# MCU_main-Sheet_1.net
KiCad netlist of a schematic drawn in Altium Designer
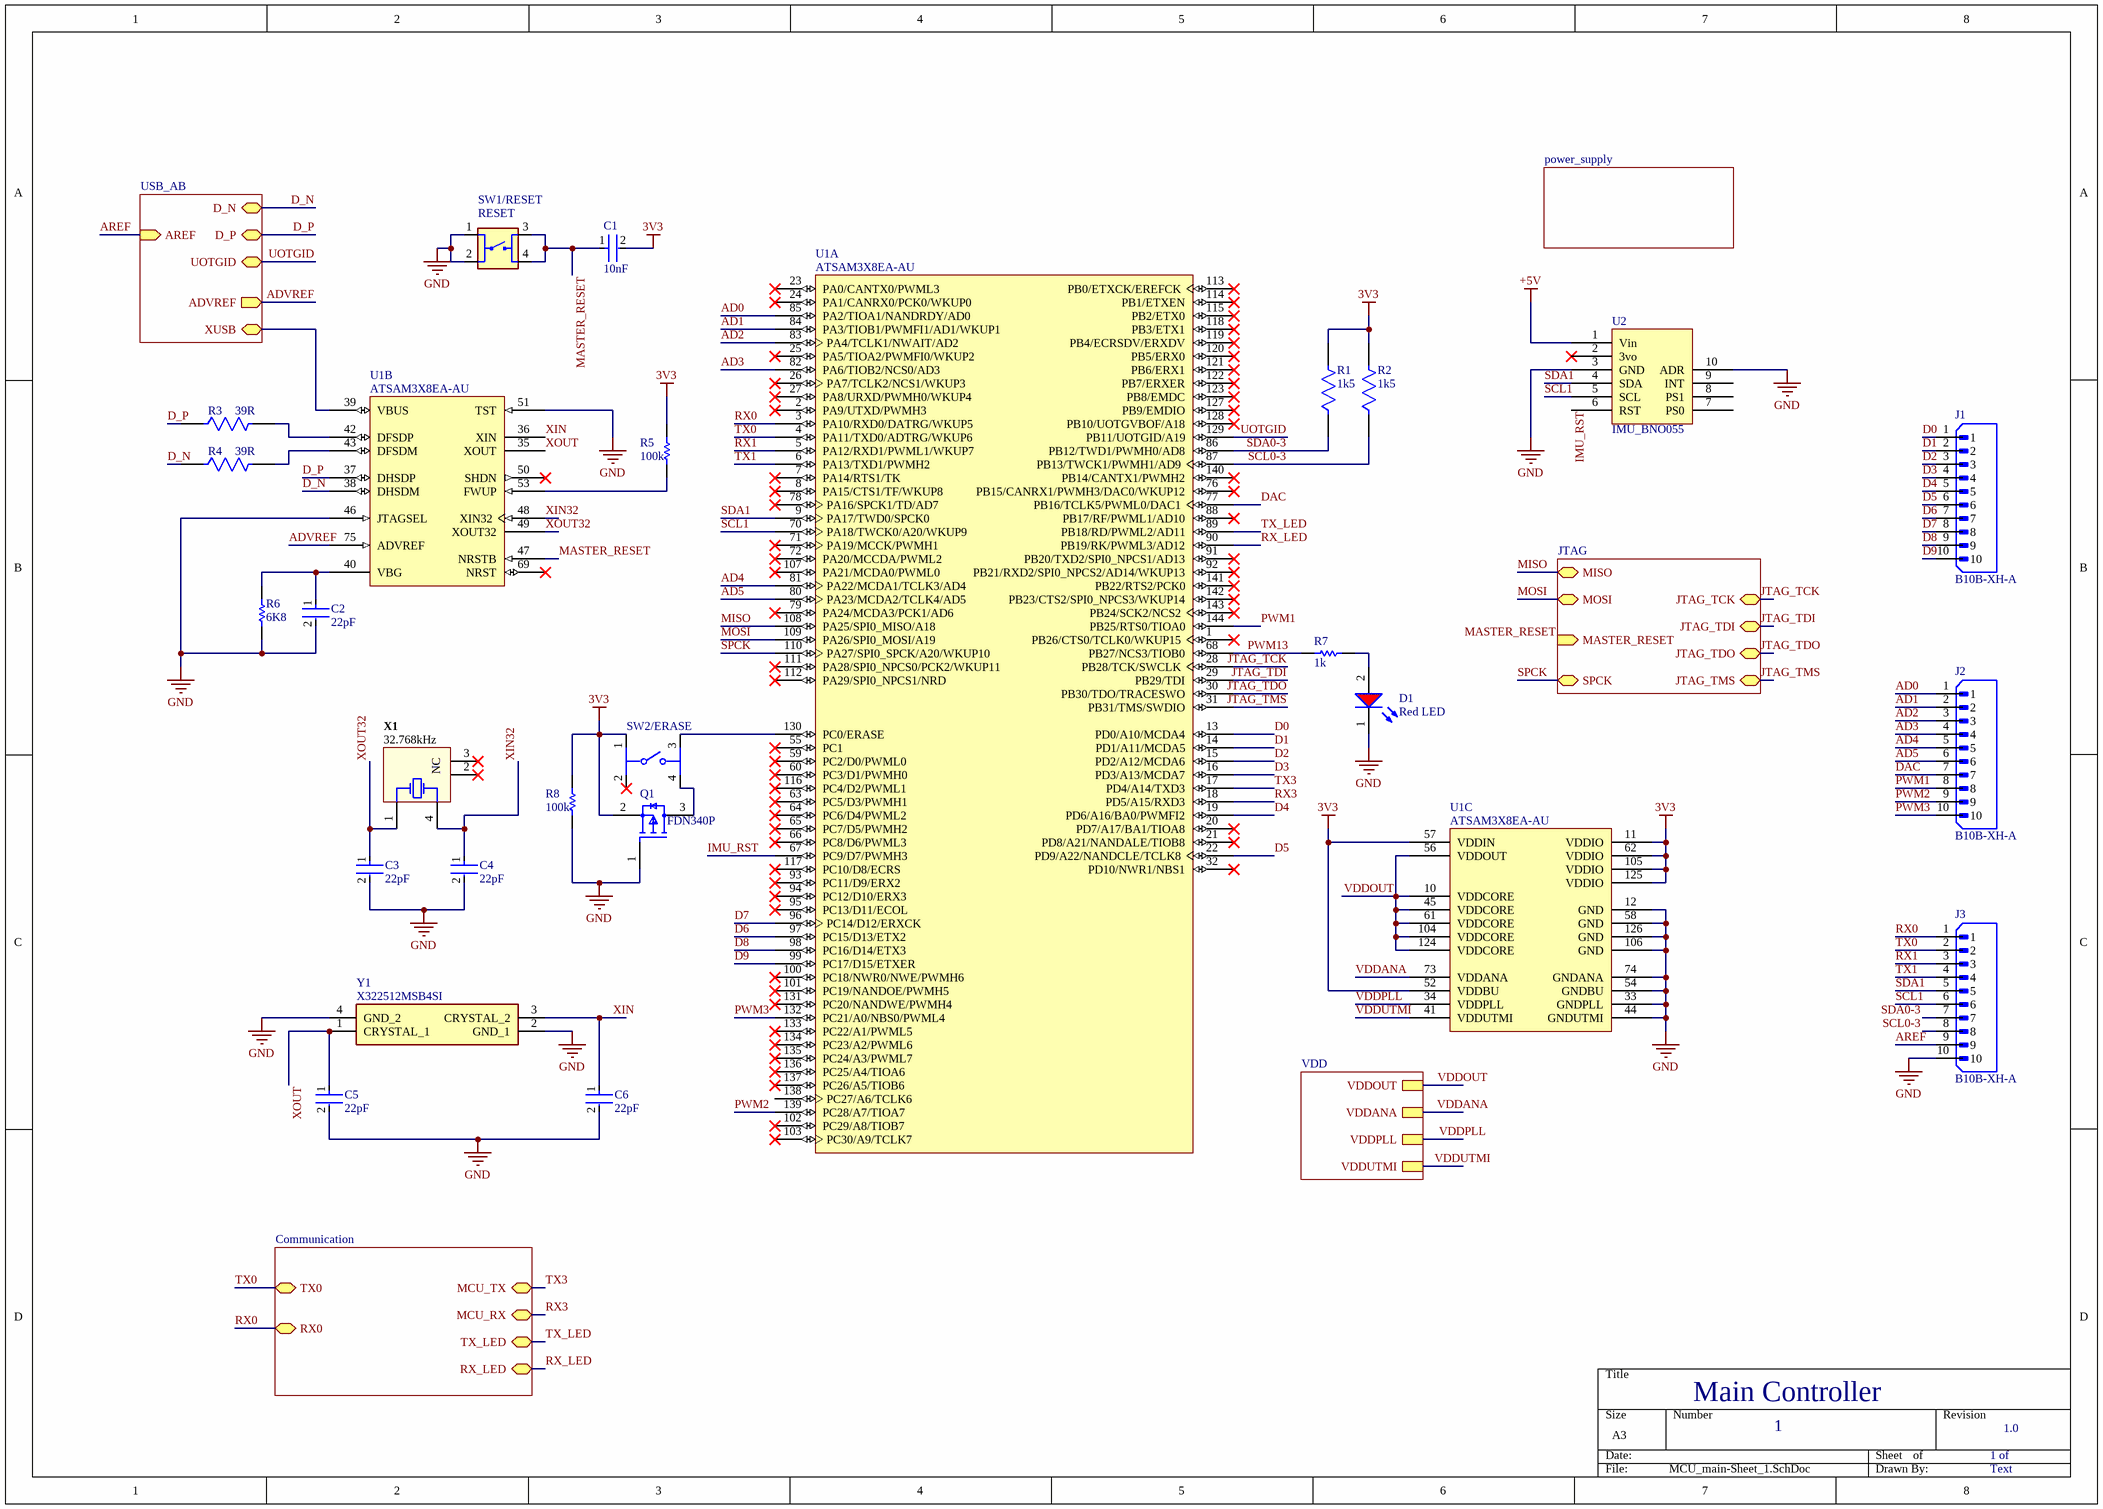
[diagram p0:  MCU_main-Sheet_1.SchDoc]

(export (version "E")
  (design (tool "Eeschema 10.0.6"))
  (components
    (comp (ref "C1")
      (value "10nF")
      (footprint "FP-C0805C-DN-MFG")
      (description "CAP CER 10000PF 200V X7R 0805")
      (fields
        (field (name "OCTOPART") "https://octopart.com/c0805c103k2ractu-kemet-9138347")
        (field (name "MANUFACTURER PART NUMBER") "C0805C103K2RACTU")
      )
      (libsource (lib "Altium Content Vault") (part "b4654b650e69147ec39a6b967a45e02"))
    )
    (comp (ref "C2")
      (value "22pF")
      (footprint "FP-C0805C-DN-MFG")
      (description "Capacitor; Ceramic; Cap; 22.0pF; Tol 5%; SMT; Vol-Rtg 50V; C0G; Tape and Reel")
      (fields
        (field (name "OCTOPART") "https://octopart.com/c0805c220j5gactu-kemet-145470")
        (field (name "MANUFACTURER") "KEMET")
      )
      (libsource (lib "Altium Content Vault") (part "b4654b650e69147ec39a6b967a45e02"))
    )
    (comp (ref "C3")
      (value "22pF")
      (footprint "FP-C0805C-DN-MFG")
      (description "Capacitor; Ceramic; Cap; 22.0pF; Tol 5%; SMT; Vol-Rtg 50V; C0G; Tape and Reel")
      (fields
        (field (name "OCTOPART") "https://octopart.com/c0805c220j5gactu-kemet-145470")
        (field (name "MANUFACTURER") "KEMET")
      )
      (libsource (lib "Altium Content Vault") (part "b4654b650e69147ec39a6b967a45e02"))
    )
    (comp (ref "C4")
      (value "22pF")
      (footprint "FP-C0805C-DN-MFG")
      (description "Capacitor; Ceramic; Cap; 22.0pF; Tol 5%; SMT; Vol-Rtg 50V; C0G; Tape and Reel")
      (fields
        (field (name "OCTOPART") "https://octopart.com/c0805c220j5gactu-kemet-145470")
        (field (name "MANUFACTURER") "KEMET")
      )
      (libsource (lib "Altium Content Vault") (part "b4654b650e69147ec39a6b967a45e02"))
    )
    (comp (ref "C5")
      (value "22pF")
      (footprint "FP-C0805C-DN-MFG")
      (description "Capacitor; Ceramic; Cap; 22.0pF; Tol 5%; SMT; Vol-Rtg 50V; C0G; Tape and Reel")
      (fields
        (field (name "OCTOPART") "https://octopart.com/c0805c220j5gactu-kemet-145470")
        (field (name "MANUFACTURER") "KEMET")
      )
      (libsource (lib "Altium Content Vault") (part "b4654b650e69147ec39a6b967a45e02"))
    )
    (comp (ref "C6")
      (value "22pF")
      (footprint "FP-C0805C-DN-MFG")
      (description "Capacitor; Ceramic; Cap; 22.0pF; Tol 5%; SMT; Vol-Rtg 50V; C0G; Tape and Reel")
      (fields
        (field (name "OCTOPART") "https://octopart.com/c0805c220j5gactu-kemet-145470")
        (field (name "MANUFACTURER") "KEMET")
      )
      (libsource (lib "Altium Content Vault") (part "b4654b650e69147ec39a6b967a45e02"))
    )
    (comp (ref "D1")
      (value "Red LED")
      (footprint "WL-SMCW_0603_150060xx75000")
      (description "LED Low-Power Uni-Color Red 630nm 2V 2-Pin Chip 0603(1608Metric) T/R")
      (libsource (lib "Altium Content Vault") (part "LED_Red_2A-1K"))
    )
    (comp (ref "J1")
      (value "B10B-XH-A")
      (footprint "JST_B10B-XH-A")
      (fields (field (name "MF") "{'manufacturer': u'JST Sales America Inc.'}"))
      (libsource (lib "B10B-XH-A") (part "B10B-XH-A"))
    )
    (comp (ref "J2")
      (value "B10B-XH-A")
      (footprint "JST_B10B-XH-A")
      (fields (field (name "MF") "{'manufacturer': u'JST Sales America Inc.'}"))
      (libsource (lib "B10B-XH-A") (part "B10B-XH-A"))
    )
    (comp (ref "J3")
      (value "B10B-XH-A")
      (footprint "JST_B10B-XH-A")
      (fields (field (name "MF") "{'manufacturer': u'JST Sales America Inc.'}"))
      (libsource (lib "B10B-XH-A") (part "B10B-XH-A"))
    )
    (comp (ref "Q1")
      (value "FDN340P")
      (footprint "FP-527AG-MFG")
      (description "MOSFET P-CH 20V 2A SSOT3")
      (libsource (lib "Altium Content Vault") (part "d23f43cc42f60b967b7caccf14518fd"))
    )
    (comp (ref "R1")
      (value "1k5")
      (footprint "FP-RT0805-MFG")
      (description "RES SMD 1.5K OHM 0.25% 1/8W 0805")
      (fields
        (field (name "OCTOPART") "https://octopart.com/rt0805cre071k5l-yageo-1182744")
        (field (name "MANUFACTURER PART NUMBER") "RT0805CRE071K5L")
      )
      (libsource (lib "Altium Content Vault") (part "1029c3af85768c4190bb7ad29bc67b5"))
    )
    (comp (ref "R2")
      (value "1k5")
      (footprint "FP-RT0805-MFG")
      (description "RES SMD 1.5K OHM 0.25% 1/8W 0805")
      (fields
        (field (name "OCTOPART") "https://octopart.com/rt0805cre071k5l-yageo-1182744")
        (field (name "MANUFACTURER PART NUMBER") "RT0805CRE071K5L")
      )
      (libsource (lib "Altium Content Vault") (part "1029c3af85768c4190bb7ad29bc67b5"))
    )
    (comp (ref "R3")
      (value "39R")
      (footprint "FP-RK73H2A-MFG")
      (description "39Ω ±1% 0.25W Chip Resistor 0805 Flat Chip (Anti-Sulfuration) AEC-Q200 Qualified")
      (fields (field (name "TOLERANCE") "1%"))
      (libsource (lib "Altium Content Vault") (part "1029c3af85768c4190bb7ad29bc67b5"))
    )
    (comp (ref "R4")
      (value "39R")
      (footprint "FP-RK73H2A-MFG")
      (description "39Ω ±1% 0.25W Chip Resistor 0805 Flat Chip (Anti-Sulfuration) AEC-Q200 Qualified")
      (fields (field (name "TOLERANCE") "1%"))
      (libsource (lib "Altium Content Vault") (part "1029c3af85768c4190bb7ad29bc67b5"))
    )
    (comp (ref "R5")
      (value "100k")
      (footprint "RESC2013X50X30ML20T20")
      (fields (field (name "MANUFACTURER") "Vishay Dale") (field (name "PART NUMBER") "CRCW0805100KJNEA"))
      (libsource (lib "Altium Content Vault") (part "RES"))
    )
    (comp (ref "R6")
      (value "6K8")
      (footprint "RESC2013X50X30LL20T20")
      (fields (field (name "MANUFACTURER") "Vishay Dale") (field (name "PART NUMBER") "CRCW08056K80JNEA"))
      (libsource (lib "Altium Content Vault") (part "RES"))
    )
    (comp (ref "R7")
      (value "1k")
      (footprint "RESC2013X60X35ML10T20")
      (description "Chip Resistor, 1 KOhm, +/- 1%, 125 mW, -55 to 155 degC, 0805 (2012 Metric), RoHS, Tape and Reel")
      (fields (field (name "TOLERANCE") "1%") (field (name "MANUFACTURER") "Yageo"))
      (libsource (lib "Altium Content Vault") (part "RES-2"))
    )
    (comp (ref "R8")
      (value "100k")
      (footprint "RESC2013X50X30ML20T20")
      (fields (field (name "MANUFACTURER") "Vishay Dale") (field (name "PART NUMBER") "CRCW0805100KJNEA"))
      (libsource (lib "Altium Content Vault") (part "RES"))
    )
    (comp (ref "SW1/RESET")
      (value "RESET")
      (footprint "TE_4-1437565-9")
      (description "Alcoswitch, Switch, Tactile, 50 mA, SPST, Pushbutton, Off[On], FSM6JSMA ¦ TE Connectivity FSM6JSMA")
      (fields (field (name "MF") "TE Connectivity") (field (name "MP") "FSM6JSMA"))
      (libsource (lib "4-1437565-9") (part "4-1437565-9"))
    )
    (comp (ref "SW2/ERASE")
      (value "3-1825910-1")
      (footprint "FP-3-1825910-1-MFG")
      (description "SWITCH TACTILE SPST-NO 0.05A 24V")
      (fields
        (field (name "MANUFACTURER") "TE Connectivity")
        (field (name "OCTOPART") "https://octopart.com/3-1825910-1-te+connectivity-46506874")
      )
      (libsource (lib "Altium Content Vault") (part "b8895f3f4cefb76e1819d2863dba89b"))
    )
    (comp (ref "U1")
      (value "ATSAM3X8EA-AU")
      (footprint "LQFP144_M")
      (fields (field (name "MANUFACTURER") "Atmel"))
      (libsource (lib "Altium Content Vault") (part "ATML-ATSAM3X-LQFP-144"))
    )
    (comp (ref "U2")
      (value "IMU_BNO055")
      (footprint "IMU_BNO055-Footprint-1")
      (description "IMU Sensor")
      (libsource (lib "EDR_Omni_Robot") (part "IMU_BNO055-Symbol-1"))
    )
    (comp (ref "X1")
      (value "32.768kHz")
      (footprint "ABRA-ABS25-4_V")
      (fields (field (name "TOLERANCE") "20PPM") (field (name "MANUFACTURER") "Abracon"))
      (libsource (lib "Altium Content Vault") (part "ABRA-XTAL_1-4-4"))
    )
    (comp (ref "Y1")
      (value "X322512MSB4SI")
      (footprint "SamacSys:X322512MSB4SI")
      (description "Crystal or Oscillator")
      (libsource (lib "*") (part "X322512MSB4SI"))
    )
  )
  (nets
    (net (code "1") (name "+5V") (class "Default")
      (node (ref "U2") (pin "1") (pinfunction "Vin_1") (pintype "passive"))
    )
    (net (code "2") (name "/AD0") (class "Default")
      (node (ref "J2") (pin "1") (pinfunction "1_1") (pintype "passive"))
      (node (ref "U1") (pin "85") (pinfunction "PA2/TIOA1/NANDRDY/AD0_85") (pintype "bidirectional"))
    )
    (net (code "3") (name "/AD1") (class "Default")
      (node (ref "J2") (pin "2") (pinfunction "2_2") (pintype "passive"))
      (node (ref "U1") (pin "84") (pinfunction "PA3/TIOB1/PWMFI1/AD1/WKUP1_84") (pintype "bidirectional"))
    )
    (net (code "4") (name "/AD2") (class "Default")
      (node (ref "J2") (pin "3") (pinfunction "3_3") (pintype "passive"))
      (node (ref "U1") (pin "83") (pinfunction "PA4/TCLK1/NWAIT/AD2_83") (pintype "bidirectional"))
    )
    (net (code "5") (name "/AD3") (class "Default")
      (node (ref "J2") (pin "4") (pinfunction "4_4") (pintype "passive"))
      (node (ref "U1") (pin "82") (pinfunction "PA6/TIOB2/NCS0/AD3_82") (pintype "bidirectional"))
    )
    (net (code "6") (name "/AD4") (class "Default")
      (node (ref "J2") (pin "5") (pinfunction "5_5") (pintype "passive"))
      (node (ref "U1") (pin "81") (pinfunction "PA22/MCDA1/TCLK3/AD4_81") (pintype "bidirectional"))
    )
    (net (code "7") (name "/AD5") (class "Default")
      (node (ref "J2") (pin "6") (pinfunction "6_6") (pintype "passive"))
      (node (ref "U1") (pin "80") (pinfunction "PA23/MCDA2/TCLK4/AD5_80") (pintype "bidirectional"))
    )
    (net (code "8") (name "/ADVREF") (class "Default")
      (node (ref "U1") (pin "75") (pinfunction "ADVREF_75") (pintype "input"))
    )
    (net (code "9") (name "/AREF") (class "Default")
      (node (ref "J3") (pin "9") (pinfunction "9_9") (pintype "passive"))
    )
    (net (code "10") (name "/D0") (class "Default")
      (node (ref "J1") (pin "1") (pinfunction "1_1") (pintype "passive"))
      (node (ref "U1") (pin "13") (pinfunction "PD0/A10/MCDA4_13") (pintype "bidirectional"))
    )
    (net (code "11") (name "/D1") (class "Default")
      (node (ref "J1") (pin "2") (pinfunction "2_2") (pintype "passive"))
      (node (ref "U1") (pin "14") (pinfunction "PD1/A11/MCDA5_14") (pintype "bidirectional"))
    )
    (net (code "12") (name "/D2") (class "Default")
      (node (ref "J1") (pin "3") (pinfunction "3_3") (pintype "passive"))
      (node (ref "U1") (pin "15") (pinfunction "PD2/A12/MCDA6_15") (pintype "bidirectional"))
    )
    (net (code "13") (name "/D3") (class "Default")
      (node (ref "J1") (pin "4") (pinfunction "4_4") (pintype "passive"))
      (node (ref "U1") (pin "16") (pinfunction "PD3/A13/MCDA7_16") (pintype "bidirectional"))
    )
    (net (code "14") (name "/D4") (class "Default")
      (node (ref "J1") (pin "5") (pinfunction "5_5") (pintype "passive"))
      (node (ref "U1") (pin "19") (pinfunction "PD6/A16/BA0/PWMFI2_19") (pintype "bidirectional"))
    )
    (net (code "15") (name "/D5") (class "Default")
      (node (ref "J1") (pin "6") (pinfunction "6_6") (pintype "passive"))
      (node (ref "U1") (pin "22") (pinfunction "PD9/A22/NANDCLE/TCLK8_22") (pintype "bidirectional"))
    )
    (net (code "16") (name "/D6") (class "Default")
      (node (ref "J1") (pin "7") (pinfunction "7_7") (pintype "passive"))
      (node (ref "U1") (pin "97") (pinfunction "PC15/D13/ETX2_97") (pintype "bidirectional"))
    )
    (net (code "17") (name "/D7") (class "Default")
      (node (ref "J1") (pin "8") (pinfunction "8_8") (pintype "passive"))
      (node (ref "U1") (pin "96") (pinfunction "PC14/D12/ERXCK_96") (pintype "bidirectional"))
    )
    (net (code "18") (name "/D8") (class "Default")
      (node (ref "J1") (pin "9") (pinfunction "9_9") (pintype "passive"))
      (node (ref "U1") (pin "98") (pinfunction "PC16/D14/ETX3_98") (pintype "bidirectional"))
    )
    (net (code "19") (name "/D9") (class "Default")
      (node (ref "J1") (pin "10") (pinfunction "10_10") (pintype "passive"))
      (node (ref "U1") (pin "99") (pinfunction "PC17/D15/ETXER_99") (pintype "bidirectional"))
    )
    (net (code "20") (name "/DAC") (class "Default")
      (node (ref "J2") (pin "7") (pinfunction "7_7") (pintype "passive"))
      (node (ref "U1") (pin "77") (pinfunction "PB16/TCLK5/PWML0/DAC1_77") (pintype "bidirectional"))
    )
    (net (code "21") (name "/D_N") (class "Default")
      (node (ref "R4") (pin "1") (pinfunction "1_1") (pintype "passive"))
      (node (ref "U1") (pin "38") (pinfunction "DHSDM_38") (pintype "bidirectional"))
    )
    (net (code "22") (name "/D_P") (class "Default")
      (node (ref "R3") (pin "1") (pinfunction "1_1") (pintype "passive"))
      (node (ref "U1") (pin "37") (pinfunction "DHSDP_37") (pintype "bidirectional"))
    )
    (net (code "23") (name "/IMU_RST") (class "Default")
      (node (ref "U1") (pin "67") (pinfunction "PC9/D7/PWMH3_67") (pintype "bidirectional"))
      (node (ref "U2") (pin "6") (pinfunction "RST_6") (pintype "passive"))
    )
    (net (code "24") (name "/JTAG_TCK") (class "Default")
      (node (ref "U1") (pin "28") (pinfunction "PB28/TCK/SWCLK_28") (pintype "bidirectional"))
    )
    (net (code "25") (name "/JTAG_TDI") (class "Default")
      (node (ref "U1") (pin "29") (pinfunction "PB29/TDI_29") (pintype "bidirectional"))
    )
    (net (code "26") (name "/JTAG_TDO") (class "Default")
      (node (ref "U1") (pin "30") (pinfunction "PB30/TDO/TRACESWO_30") (pintype "bidirectional"))
    )
    (net (code "27") (name "/JTAG_TMS") (class "Default")
      (node (ref "U1") (pin "31") (pinfunction "PB31/TMS/SWDIO_31") (pintype "bidirectional"))
    )
    (net (code "28") (name "/MASTER_RESET") (class "Default")
      (node (ref "C1") (pin "1") (pinfunction "1_1") (pintype "passive"))
      (node (ref "SW1/RESET") (pin "3") (pinfunction "3_3") (pintype "passive"))
      (node (ref "SW1/RESET") (pin "4") (pinfunction "4_4") (pintype "passive"))
      (node (ref "U1") (pin "47") (pinfunction "NRSTB_47") (pintype "input"))
    )
    (net (code "29") (name "/MISO") (class "Default")
      (node (ref "U1") (pin "108") (pinfunction "PA25/SPI0_MISO/A18_108") (pintype "bidirectional"))
    )
    (net (code "30") (name "/MOSI") (class "Default")
      (node (ref "U1") (pin "109") (pinfunction "PA26/SPI0_MOSI/A19_109") (pintype "bidirectional"))
    )
    (net (code "31") (name "/PWM1") (class "Default")
      (node (ref "J2") (pin "8") (pinfunction "8_8") (pintype "passive"))
      (node (ref "U1") (pin "144") (pinfunction "PB25/RTS0/TIOA0_144") (pintype "bidirectional"))
    )
    (net (code "32") (name "/PWM2") (class "Default")
      (node (ref "J2") (pin "9") (pinfunction "9_9") (pintype "passive"))
      (node (ref "U1") (pin "139") (pinfunction "PC28/A7/TIOA7_139") (pintype "bidirectional"))
    )
    (net (code "33") (name "/PWM3") (class "Default")
      (node (ref "J2") (pin "10") (pinfunction "10_10") (pintype "passive"))
      (node (ref "U1") (pin "132") (pinfunction "PC21/A0/NBS0/PWML4_132") (pintype "bidirectional"))
    )
    (net (code "34") (name "/PWM13") (class "Default")
      (node (ref "R7") (pin "2") (pinfunction "2_2") (pintype "passive"))
      (node (ref "U1") (pin "68") (pinfunction "PB27/NCS3/TIOB0_68") (pintype "bidirectional"))
    )
    (net (code "35") (name "/RX0") (class "Default")
      (node (ref "J3") (pin "1") (pinfunction "1_1") (pintype "passive"))
      (node (ref "U1") (pin "3") (pinfunction "PA10/RXD0/DATRG/WKUP5_3") (pintype "bidirectional"))
    )
    (net (code "36") (name "/RX1") (class "Default")
      (node (ref "J3") (pin "3") (pinfunction "3_3") (pintype "passive"))
      (node (ref "U1") (pin "5") (pinfunction "PA12/RXD1/PWML1/WKUP7_5") (pintype "bidirectional"))
    )
    (net (code "37") (name "/RX3") (class "Default")
      (node (ref "U1") (pin "18") (pinfunction "PD5/A15/RXD3_18") (pintype "bidirectional"))
    )
    (net (code "38") (name "/RX_LED") (class "Default")
      (node (ref "U1") (pin "90") (pinfunction "PB19/RK/PWML3/AD12_90") (pintype "bidirectional"))
    )
    (net (code "39") (name "/SCL0-3") (class "Default")
      (node (ref "J3") (pin "8") (pinfunction "8_8") (pintype "passive"))
      (node (ref "R2") (pin "1") (pinfunction "1_1") (pintype "passive"))
      (node (ref "U1") (pin "87") (pinfunction "PB13/TWCK1/PWMH1/AD9_87") (pintype "bidirectional"))
    )
    (net (code "40") (name "/SCL1") (class "Default")
      (node (ref "J3") (pin "6") (pinfunction "6_6") (pintype "passive"))
      (node (ref "U1") (pin "70") (pinfunction "PA18/TWCK0/A20/WKUP9_70") (pintype "bidirectional"))
      (node (ref "U2") (pin "5") (pinfunction "SCL_5") (pintype "passive"))
    )
    (net (code "41") (name "/SDA0-3") (class "Default")
      (node (ref "J3") (pin "7") (pinfunction "7_7") (pintype "passive"))
      (node (ref "R1") (pin "1") (pinfunction "1_1") (pintype "passive"))
      (node (ref "U1") (pin "86") (pinfunction "PB12/TWD1/PWMH0/AD8_86") (pintype "bidirectional"))
    )
    (net (code "42") (name "/SDA1") (class "Default")
      (node (ref "J3") (pin "5") (pinfunction "5_5") (pintype "passive"))
      (node (ref "U1") (pin "9") (pinfunction "PA17/TWD0/SPCK0_9") (pintype "bidirectional"))
      (node (ref "U2") (pin "4") (pinfunction "SDA_4") (pintype "passive"))
    )
    (net (code "43") (name "/SPCK") (class "Default")
      (node (ref "U1") (pin "110") (pinfunction "PA27/SPI0_SPCK/A20/WKUP10_110") (pintype "bidirectional"))
    )
    (net (code "44") (name "/TX0") (class "Default")
      (node (ref "J3") (pin "2") (pinfunction "2_2") (pintype "passive"))
      (node (ref "U1") (pin "4") (pinfunction "PA11/TXD0/ADTRG/WKUP6_4") (pintype "bidirectional"))
    )
    (net (code "45") (name "/TX1") (class "Default")
      (node (ref "J3") (pin "4") (pinfunction "4_4") (pintype "passive"))
      (node (ref "U1") (pin "6") (pinfunction "PA13/TXD1/PWMH2_6") (pintype "bidirectional"))
    )
    (net (code "46") (name "/TX3") (class "Default")
      (node (ref "U1") (pin "17") (pinfunction "PD4/A14/TXD3_17") (pintype "bidirectional"))
    )
    (net (code "47") (name "/TX_LED") (class "Default")
      (node (ref "U1") (pin "89") (pinfunction "PB18/RD/PWML2/AD11_89") (pintype "bidirectional"))
    )
    (net (code "48") (name "/UOTGID") (class "Default")
      (node (ref "U1") (pin "129") (pinfunction "PB11/UOTGID/A19_129") (pintype "bidirectional"))
    )
    (net (code "49") (name "/VDDANA") (class "Default")
      (node (ref "U1") (pin "73") (pinfunction "VDDANA_73") (pintype "power_in"))
    )
    (net (code "50") (name "/VDDOUT") (class "Default")
      (node (ref "U1") (pin "10") (pinfunction "VDDCORE_10") (pintype "power_in"))
      (node (ref "U1") (pin "104") (pinfunction "VDDCORE_104") (pintype "power_in"))
      (node (ref "U1") (pin "124") (pinfunction "VDDCORE_124") (pintype "power_in"))
      (node (ref "U1") (pin "45") (pinfunction "VDDCORE_45") (pintype "power_in"))
      (node (ref "U1") (pin "56") (pinfunction "VDDOUT_56") (pintype "power_in"))
      (node (ref "U1") (pin "61") (pinfunction "VDDCORE_61") (pintype "power_in"))
    )
    (net (code "51") (name "/VDDPLL") (class "Default")
      (node (ref "U1") (pin "34") (pinfunction "VDDPLL_34") (pintype "power_in"))
    )
    (net (code "52") (name "/VDDUTMI") (class "Default")
      (node (ref "U1") (pin "41") (pinfunction "VDDUTMI_41") (pintype "power_in"))
    )
    (net (code "53") (name "/XIN") (class "Default")
      (node (ref "C6") (pin "1") (pinfunction "1_1") (pintype "passive"))
      (node (ref "U1") (pin "36") (pinfunction "XIN_36") (pintype "passive"))
      (node (ref "Y1") (pin "3") (pinfunction "CRYSTAL_2_3") (pintype "passive"))
    )
    (net (code "54") (name "/XIN32") (class "Default")
      (node (ref "C4") (pin "1") (pinfunction "1_1") (pintype "passive"))
      (node (ref "U1") (pin "48") (pinfunction "XIN32_48") (pintype "input"))
      (node (ref "X1") (pin "4") (pinfunction "X2_4") (pintype "passive"))
    )
    (net (code "55") (name "/XOUT") (class "Default")
      (node (ref "C5") (pin "1") (pinfunction "1_1") (pintype "passive"))
      (node (ref "U1") (pin "35") (pinfunction "XOUT_35") (pintype "passive"))
      (node (ref "Y1") (pin "1") (pinfunction "CRYSTAL_1_1") (pintype "passive"))
    )
    (net (code "56") (name "/XOUT32") (class "Default")
      (node (ref "C3") (pin "1") (pinfunction "1_1") (pintype "passive"))
      (node (ref "U1") (pin "49") (pinfunction "XOUT32_49") (pintype "passive"))
      (node (ref "X1") (pin "1") (pinfunction "X1_1") (pintype "passive"))
    )
    (net (code "57") (name "/XUSB") (class "Default")
      (node (ref "U1") (pin "39") (pinfunction "VBUS_39") (pintype "bidirectional"))
    )
    (net (code "58") (name "3V3") (class "Default")
      (node (ref "C1") (pin "2") (pinfunction "2_2") (pintype "passive"))
      (node (ref "Q1") (pin "2") (pinfunction "S_2") (pintype "passive"))
      (node (ref "R1") (pin "2") (pinfunction "2_2") (pintype "passive"))
      (node (ref "R2") (pin "2") (pinfunction "2_2") (pintype "passive"))
      (node (ref "R5") (pin "2") (pinfunction "2_2") (pintype "passive"))
      (node (ref "R8") (pin "2") (pinfunction "2_2") (pintype "passive"))
      (node (ref "SW2/ERASE") (pin "1") (pinfunction "1_1") (pintype "passive"))
      (node (ref "U1") (pin "105") (pinfunction "VDDIO_105") (pintype "power_in"))
      (node (ref "U1") (pin "11") (pinfunction "VDDIO_11") (pintype "power_in"))
      (node (ref "U1") (pin "125") (pinfunction "VDDIO_125") (pintype "power_in"))
      (node (ref "U1") (pin "52") (pinfunction "VDDBU_52") (pintype "power_in"))
      (node (ref "U1") (pin "57") (pinfunction "VDDIN_57") (pintype "power_in"))
      (node (ref "U1") (pin "62") (pinfunction "VDDIO_62") (pintype "power_in"))
    )
    (net (code "59") (name "GND") (class "Default")
      (node (ref "C2") (pin "2") (pinfunction "2_2") (pintype "passive"))
      (node (ref "C3") (pin "2") (pinfunction "2_2") (pintype "passive"))
      (node (ref "C4") (pin "2") (pinfunction "2_2") (pintype "passive"))
      (node (ref "C5") (pin "2") (pinfunction "2_2") (pintype "passive"))
      (node (ref "C6") (pin "2") (pinfunction "2_2") (pintype "passive"))
      (node (ref "D1") (pin "1") (pinfunction "K_1") (pintype "passive"))
      (node (ref "J3") (pin "10") (pinfunction "10_10") (pintype "passive"))
      (node (ref "Q1") (pin "1") (pinfunction "G_1") (pintype "passive"))
      (node (ref "R6") (pin "1") (pinfunction "1_1") (pintype "passive"))
      (node (ref "R8") (pin "1") (pinfunction "1_1") (pintype "passive"))
      (node (ref "SW1/RESET") (pin "1") (pinfunction "1_1") (pintype "passive"))
      (node (ref "SW1/RESET") (pin "2") (pinfunction "2_2") (pintype "passive"))
      (node (ref "U1") (pin "106") (pinfunction "GND_106") (pintype "power_in"))
      (node (ref "U1") (pin "12") (pinfunction "GND_12") (pintype "power_in"))
      (node (ref "U1") (pin "126") (pinfunction "GND_126") (pintype "power_in"))
      (node (ref "U1") (pin "33") (pinfunction "GNDPLL_33") (pintype "power_in"))
      (node (ref "U1") (pin "44") (pinfunction "GNDUTMI_44") (pintype "power_in"))
      (node (ref "U1") (pin "46") (pinfunction "JTAGSEL_46") (pintype "input"))
      (node (ref "U1") (pin "51") (pinfunction "TST_51") (pintype "input"))
      (node (ref "U1") (pin "54") (pinfunction "GNDBU_54") (pintype "power_in"))
      (node (ref "U1") (pin "58") (pinfunction "GND_58") (pintype "power_in"))
      (node (ref "U1") (pin "74") (pinfunction "GNDANA_74") (pintype "power_in"))
      (node (ref "U2") (pin "10") (pinfunction "ADR_10") (pintype "passive"))
      (node (ref "U2") (pin "3") (pinfunction "GND_3") (pintype "passive"))
      (node (ref "Y1") (pin "2") (pinfunction "GND_1_2") (pintype "passive"))
      (node (ref "Y1") (pin "4") (pinfunction "GND_2_4") (pintype "passive"))
    )
    (net (code "60") (name "Net-(D1-A)") (class "Default")
      (node (ref "D1") (pin "2") (pinfunction "A_2") (pintype "passive"))
      (node (ref "R7") (pin "1") (pinfunction "1_1") (pintype "passive"))
    )
    (net (code "61") (name "Net-(Q1-D)") (class "Default")
      (node (ref "Q1") (pin "3") (pinfunction "D_3") (pintype "passive"))
      (node (ref "SW2/ERASE") (pin "4") (pinfunction "4_4") (pintype "passive"))
    )
    (net (code "62") (name "Net-(U1A-PC0{slash}ERASE)") (class "Default")
      (node (ref "SW2/ERASE") (pin "3") (pinfunction "3_3") (pintype "passive"))
      (node (ref "U1") (pin "130") (pinfunction "PC0/ERASE_130") (pintype "bidirectional"))
    )
    (net (code "63") (name "Net-(U1B-DFSDM)") (class "Default")
      (node (ref "R4") (pin "2") (pinfunction "2_2") (pintype "passive"))
      (node (ref "U1") (pin "43") (pinfunction "DFSDM_43") (pintype "bidirectional"))
    )
    (net (code "64") (name "Net-(U1B-DFSDP)") (class "Default")
      (node (ref "R3") (pin "2") (pinfunction "2_2") (pintype "passive"))
      (node (ref "U1") (pin "42") (pinfunction "DFSDP_42") (pintype "bidirectional"))
    )
    (net (code "65") (name "Net-(U1B-FWUP)") (class "Default")
      (node (ref "R5") (pin "1") (pinfunction "1_1") (pintype "passive"))
      (node (ref "U1") (pin "53") (pinfunction "FWUP_53") (pintype "input"))
    )
    (net (code "66") (name "Net-(U1B-VBG)") (class "Default")
      (node (ref "C2") (pin "1") (pinfunction "1_1") (pintype "passive"))
      (node (ref "R6") (pin "2") (pinfunction "2_2") (pintype "passive"))
      (node (ref "U1") (pin "40") (pinfunction "VBG_40") (pintype "passive"))
    )
    (net (code "67") (name "unconnected-(SW2/ERASE-Pad2)") (class "Default")
      (node (ref "SW2/ERASE") (pin "2") (pinfunction "2_2") (pintype "passive+no_connect"))
    )
    (net (code "68") (name "unconnected-(U1A-PA0{slash}CANTX0{slash}PWML3-Pad23)") (class "Default")
      (node (ref "U1") (pin "23") (pinfunction "PA0/CANTX0/PWML3_23") (pintype "bidirectional+no_connect"))
    )
    (net (code "69") (name "unconnected-(U1A-PA1{slash}CANRX0{slash}PCK0{slash}WKUP0-Pad24)") (class "Default")
      (node (ref "U1") (pin "24") (pinfunction "PA1/CANRX0/PCK0/WKUP0_24") (pintype "bidirectional+no_connect"))
    )
    (net (code "70") (name "unconnected-(U1A-PA5{slash}TIOA2{slash}PWMFI0{slash}WKUP2-Pad25)") (class "Default")
      (node (ref "U1") (pin "25") (pinfunction "PA5/TIOA2/PWMFI0/WKUP2_25") (pintype "bidirectional+no_connect"))
    )
    (net (code "71") (name "unconnected-(U1A-PA7{slash}TCLK2{slash}NCS1{slash}WKUP3-Pad26)") (class "Default")
      (node (ref "U1") (pin "26") (pinfunction "PA7/TCLK2/NCS1/WKUP3_26") (pintype "bidirectional+no_connect"))
    )
    (net (code "72") (name "unconnected-(U1A-PA8{slash}URXD{slash}PWMH0{slash}WKUP4-Pad27)") (class "Default")
      (node (ref "U1") (pin "27") (pinfunction "PA8/URXD/PWMH0/WKUP4_27") (pintype "bidirectional+no_connect"))
    )
    (net (code "73") (name "unconnected-(U1A-PA9{slash}UTXD{slash}PWMH3-Pad2)") (class "Default")
      (node (ref "U1") (pin "2") (pinfunction "PA9/UTXD/PWMH3_2") (pintype "bidirectional+no_connect"))
    )
    (net (code "74") (name "unconnected-(U1A-PA14{slash}RTS1{slash}TK-Pad7)") (class "Default")
      (node (ref "U1") (pin "7") (pinfunction "PA14/RTS1/TK_7") (pintype "bidirectional+no_connect"))
    )
    (net (code "75") (name "unconnected-(U1A-PA15{slash}CTS1{slash}TF{slash}WKUP8-Pad8)") (class "Default")
      (node (ref "U1") (pin "8") (pinfunction "PA15/CTS1/TF/WKUP8_8") (pintype "bidirectional+no_connect"))
    )
    (net (code "76") (name "unconnected-(U1A-PA16{slash}SPCK1{slash}TD{slash}AD7-Pad78)") (class "Default")
      (node (ref "U1") (pin "78") (pinfunction "PA16/SPCK1/TD/AD7_78") (pintype "bidirectional+no_connect"))
    )
    (net (code "77") (name "unconnected-(U1A-PA19{slash}MCCK{slash}PWMH1-Pad71)") (class "Default")
      (node (ref "U1") (pin "71") (pinfunction "PA19/MCCK/PWMH1_71") (pintype "bidirectional+no_connect"))
    )
    (net (code "78") (name "unconnected-(U1A-PA20{slash}MCCDA{slash}PWML2-Pad72)") (class "Default")
      (node (ref "U1") (pin "72") (pinfunction "PA20/MCCDA/PWML2_72") (pintype "bidirectional+no_connect"))
    )
    (net (code "79") (name "unconnected-(U1A-PA21{slash}MCDA0{slash}PWML0-Pad107)") (class "Default")
      (node (ref "U1") (pin "107") (pinfunction "PA21/MCDA0/PWML0_107") (pintype "bidirectional+no_connect"))
    )
    (net (code "80") (name "unconnected-(U1A-PA24{slash}MCDA3{slash}PCK1{slash}AD6-Pad79)") (class "Default")
      (node (ref "U1") (pin "79") (pinfunction "PA24/MCDA3/PCK1/AD6_79") (pintype "bidirectional+no_connect"))
    )
    (net (code "81") (name "unconnected-(U1A-PA28{slash}SPI0_NPCS0{slash}PCK2{slash}WKUP11-Pad111)") (class "Default")
      (node (ref "U1") (pin "111") (pinfunction "PA28/SPI0_NPCS0/PCK2/WKUP11_111") (pintype "bidirectional+no_connect"))
    )
    (net (code "82") (name "unconnected-(U1A-PA29{slash}SPI0_NPCS1{slash}NRD-Pad112)") (class "Default")
      (node (ref "U1") (pin "112") (pinfunction "PA29/SPI0_NPCS1/NRD_112") (pintype "bidirectional+no_connect"))
    )
    (net (code "83") (name "unconnected-(U1A-PB0{slash}ETXCK{slash}EREFCK-Pad113)") (class "Default")
      (node (ref "U1") (pin "113") (pinfunction "PB0/ETXCK/EREFCK_113") (pintype "bidirectional+no_connect"))
    )
    (net (code "84") (name "unconnected-(U1A-PB1{slash}ETXEN-Pad114)") (class "Default")
      (node (ref "U1") (pin "114") (pinfunction "PB1/ETXEN_114") (pintype "bidirectional+no_connect"))
    )
    (net (code "85") (name "unconnected-(U1A-PB2{slash}ETX0-Pad115)") (class "Default")
      (node (ref "U1") (pin "115") (pinfunction "PB2/ETX0_115") (pintype "bidirectional+no_connect"))
    )
    (net (code "86") (name "unconnected-(U1A-PB3{slash}ETX1-Pad118)") (class "Default")
      (node (ref "U1") (pin "118") (pinfunction "PB3/ETX1_118") (pintype "bidirectional+no_connect"))
    )
    (net (code "87") (name "unconnected-(U1A-PB4{slash}ECRSDV{slash}ERXDV-Pad119)") (class "Default")
      (node (ref "U1") (pin "119") (pinfunction "PB4/ECRSDV/ERXDV_119") (pintype "bidirectional+no_connect"))
    )
    (net (code "88") (name "unconnected-(U1A-PB5{slash}ERX0-Pad120)") (class "Default")
      (node (ref "U1") (pin "120") (pinfunction "PB5/ERX0_120") (pintype "bidirectional+no_connect"))
    )
    (net (code "89") (name "unconnected-(U1A-PB6{slash}ERX1-Pad121)") (class "Default")
      (node (ref "U1") (pin "121") (pinfunction "PB6/ERX1_121") (pintype "bidirectional+no_connect"))
    )
    (net (code "90") (name "unconnected-(U1A-PB7{slash}ERXER-Pad122)") (class "Default")
      (node (ref "U1") (pin "122") (pinfunction "PB7/ERXER_122") (pintype "bidirectional+no_connect"))
    )
    (net (code "91") (name "unconnected-(U1A-PB8{slash}EMDC-Pad123)") (class "Default")
      (node (ref "U1") (pin "123") (pinfunction "PB8/EMDC_123") (pintype "bidirectional+no_connect"))
    )
    (net (code "92") (name "unconnected-(U1A-PB9{slash}EMDIO-Pad127)") (class "Default")
      (node (ref "U1") (pin "127") (pinfunction "PB9/EMDIO_127") (pintype "bidirectional+no_connect"))
    )
    (net (code "93") (name "unconnected-(U1A-PB10{slash}UOTGVBOF{slash}A18-Pad128)") (class "Default")
      (node (ref "U1") (pin "128") (pinfunction "PB10/UOTGVBOF/A18_128") (pintype "bidirectional+no_connect"))
    )
    (net (code "94") (name "unconnected-(U1A-PB14{slash}CANTX1{slash}PWMH2-Pad140)") (class "Default")
      (node (ref "U1") (pin "140") (pinfunction "PB14/CANTX1/PWMH2_140") (pintype "bidirectional+no_connect"))
    )
    (net (code "95") (name "unconnected-(U1A-PB15{slash}CANRX1{slash}PWMH3{slash}DAC0{slash}WKUP12-Pad76)") (class "Default")
      (node (ref "U1") (pin "76") (pinfunction "PB15/CANRX1/PWMH3/DAC0/WKUP12_76") (pintype "bidirectional+no_connect"))
    )
    (net (code "96") (name "unconnected-(U1A-PB17{slash}RF{slash}PWML1{slash}AD10-Pad88)") (class "Default")
      (node (ref "U1") (pin "88") (pinfunction "PB17/RF/PWML1/AD10_88") (pintype "bidirectional+no_connect"))
    )
    (net (code "97") (name "unconnected-(U1A-PB20{slash}TXD2{slash}SPI0_NPCS1{slash}AD13-Pad91)") (class "Default")
      (node (ref "U1") (pin "91") (pinfunction "PB20/TXD2/SPI0_NPCS1/AD13_91") (pintype "bidirectional+no_connect"))
    )
    (net (code "98") (name "unconnected-(U1A-PB21{slash}RXD2{slash}SPI0_NPCS2{slash}AD14{slash}WKUP13-Pad92)") (class "Default")
      (node (ref "U1") (pin "92") (pinfunction "PB21/RXD2/SPI0_NPCS2/AD14/WKUP13_92") (pintype "bidirectional+no_connect"))
    )
    (net (code "99") (name "unconnected-(U1A-PB22{slash}RTS2{slash}PCK0-Pad141)") (class "Default")
      (node (ref "U1") (pin "141") (pinfunction "PB22/RTS2/PCK0_141") (pintype "bidirectional+no_connect"))
    )
    (net (code "100") (name "unconnected-(U1A-PB23{slash}CTS2{slash}SPI0_NPCS3{slash}WKUP14-Pad142)") (class "Default")
      (node (ref "U1") (pin "142") (pinfunction "PB23/CTS2/SPI0_NPCS3/WKUP14_142") (pintype "bidirectional+no_connect"))
    )
    (net (code "101") (name "unconnected-(U1A-PB24{slash}SCK2{slash}NCS2-Pad143)") (class "Default")
      (node (ref "U1") (pin "143") (pinfunction "PB24/SCK2/NCS2_143") (pintype "bidirectional+no_connect"))
    )
    (net (code "102") (name "unconnected-(U1A-PB26{slash}CTS0{slash}TCLK0{slash}WKUP15-Pad1)") (class "Default")
      (node (ref "U1") (pin "1") (pinfunction "PB26/CTS0/TCLK0/WKUP15_1") (pintype "bidirectional+no_connect"))
    )
    (net (code "103") (name "unconnected-(U1A-PC1-Pad55)") (class "Default")
      (node (ref "U1") (pin "55") (pinfunction "PC1_55") (pintype "bidirectional+no_connect"))
    )
    (net (code "104") (name "unconnected-(U1A-PC2{slash}D0{slash}PWML0-Pad59)") (class "Default")
      (node (ref "U1") (pin "59") (pinfunction "PC2/D0/PWML0_59") (pintype "bidirectional+no_connect"))
    )
    (net (code "105") (name "unconnected-(U1A-PC3{slash}D1{slash}PWMH0-Pad60)") (class "Default")
      (node (ref "U1") (pin "60") (pinfunction "PC3/D1/PWMH0_60") (pintype "bidirectional+no_connect"))
    )
    (net (code "106") (name "unconnected-(U1A-PC4{slash}D2{slash}PWML1-Pad116)") (class "Default")
      (node (ref "U1") (pin "116") (pinfunction "PC4/D2/PWML1_116") (pintype "bidirectional+no_connect"))
    )
    (net (code "107") (name "unconnected-(U1A-PC5{slash}D3{slash}PWMH1-Pad63)") (class "Default")
      (node (ref "U1") (pin "63") (pinfunction "PC5/D3/PWMH1_63") (pintype "bidirectional+no_connect"))
    )
    (net (code "108") (name "unconnected-(U1A-PC6{slash}D4{slash}PWML2-Pad64)") (class "Default")
      (node (ref "U1") (pin "64") (pinfunction "PC6/D4/PWML2_64") (pintype "bidirectional+no_connect"))
    )
    (net (code "109") (name "unconnected-(U1A-PC7{slash}D5{slash}PWMH2-Pad65)") (class "Default")
      (node (ref "U1") (pin "65") (pinfunction "PC7/D5/PWMH2_65") (pintype "bidirectional+no_connect"))
    )
    (net (code "110") (name "unconnected-(U1A-PC8{slash}D6{slash}PWML3-Pad66)") (class "Default")
      (node (ref "U1") (pin "66") (pinfunction "PC8/D6/PWML3_66") (pintype "bidirectional+no_connect"))
    )
    (net (code "111") (name "unconnected-(U1A-PC10{slash}D8{slash}ECRS-Pad117)") (class "Default")
      (node (ref "U1") (pin "117") (pinfunction "PC10/D8/ECRS_117") (pintype "bidirectional+no_connect"))
    )
    (net (code "112") (name "unconnected-(U1A-PC11{slash}D9{slash}ERX2-Pad93)") (class "Default")
      (node (ref "U1") (pin "93") (pinfunction "PC11/D9/ERX2_93") (pintype "bidirectional+no_connect"))
    )
    (net (code "113") (name "unconnected-(U1A-PC12{slash}D10{slash}ERX3-Pad94)") (class "Default")
      (node (ref "U1") (pin "94") (pinfunction "PC12/D10/ERX3_94") (pintype "bidirectional+no_connect"))
    )
    (net (code "114") (name "unconnected-(U1A-PC13{slash}D11{slash}ECOL-Pad95)") (class "Default")
      (node (ref "U1") (pin "95") (pinfunction "PC13/D11/ECOL_95") (pintype "bidirectional+no_connect"))
    )
    (net (code "115") (name "unconnected-(U1A-PC18{slash}NWR0{slash}NWE{slash}PWMH6-Pad100)") (class "Default")
      (node (ref "U1") (pin "100") (pinfunction "PC18/NWR0/NWE/PWMH6_100") (pintype "bidirectional+no_connect"))
    )
    (net (code "116") (name "unconnected-(U1A-PC19{slash}NANDOE{slash}PWMH5-Pad101)") (class "Default")
      (node (ref "U1") (pin "101") (pinfunction "PC19/NANDOE/PWMH5_101") (pintype "bidirectional+no_connect"))
    )
    (net (code "117") (name "unconnected-(U1A-PC20{slash}NANDWE{slash}PWMH4-Pad131)") (class "Default")
      (node (ref "U1") (pin "131") (pinfunction "PC20/NANDWE/PWMH4_131") (pintype "bidirectional+no_connect"))
    )
    (net (code "118") (name "unconnected-(U1A-PC22{slash}A1{slash}PWML5-Pad133)") (class "Default")
      (node (ref "U1") (pin "133") (pinfunction "PC22/A1/PWML5_133") (pintype "bidirectional+no_connect"))
    )
    (net (code "119") (name "unconnected-(U1A-PC23{slash}A2{slash}PWML6-Pad134)") (class "Default")
      (node (ref "U1") (pin "134") (pinfunction "PC23/A2/PWML6_134") (pintype "bidirectional+no_connect"))
    )
    (net (code "120") (name "unconnected-(U1A-PC24{slash}A3{slash}PWML7-Pad135)") (class "Default")
      (node (ref "U1") (pin "135") (pinfunction "PC24/A3/PWML7_135") (pintype "bidirectional+no_connect"))
    )
    (net (code "121") (name "unconnected-(U1A-PC25{slash}A4{slash}TIOA6-Pad136)") (class "Default")
      (node (ref "U1") (pin "136") (pinfunction "PC25/A4/TIOA6_136") (pintype "bidirectional+no_connect"))
    )
    (net (code "122") (name "unconnected-(U1A-PC26{slash}A5{slash}TIOB6-Pad137)") (class "Default")
      (node (ref "U1") (pin "137") (pinfunction "PC26/A5/TIOB6_137") (pintype "bidirectional+no_connect"))
    )
    (net (code "123") (name "unconnected-(U1A-PC27{slash}A6{slash}TCLK6-Pad138)") (class "Default")
      (node (ref "U1") (pin "138") (pinfunction "PC27/A6/TCLK6_138") (pintype "bidirectional"))
    )
    (net (code "124") (name "unconnected-(U1A-PC29{slash}A8{slash}TIOB7-Pad102)") (class "Default")
      (node (ref "U1") (pin "102") (pinfunction "PC29/A8/TIOB7_102") (pintype "bidirectional+no_connect"))
    )
    (net (code "125") (name "unconnected-(U1A-PC30{slash}A9{slash}TCLK7-Pad103)") (class "Default")
      (node (ref "U1") (pin "103") (pinfunction "PC30/A9/TCLK7_103") (pintype "bidirectional+no_connect"))
    )
    (net (code "126") (name "unconnected-(U1A-PD7{slash}A17{slash}BA1{slash}TIOA8-Pad20)") (class "Default")
      (node (ref "U1") (pin "20") (pinfunction "PD7/A17/BA1/TIOA8_20") (pintype "bidirectional+no_connect"))
    )
    (net (code "127") (name "unconnected-(U1A-PD8{slash}A21{slash}NANDALE{slash}TIOB8-Pad21)") (class "Default")
      (node (ref "U1") (pin "21") (pinfunction "PD8/A21/NANDALE/TIOB8_21") (pintype "bidirectional+no_connect"))
    )
    (net (code "128") (name "unconnected-(U1A-PD10{slash}NWR1{slash}NBS1-Pad32)") (class "Default")
      (node (ref "U1") (pin "32") (pinfunction "PD10/NWR1/NBS1_32") (pintype "bidirectional+no_connect"))
    )
    (net (code "129") (name "unconnected-(U1B-NRST-Pad69)") (class "Default")
      (node (ref "U1") (pin "69") (pinfunction "NRST_69") (pintype "bidirectional+no_connect"))
    )
    (net (code "130") (name "unconnected-(U1B-SHDN-Pad50)") (class "Default")
      (node (ref "U1") (pin "50") (pinfunction "SHDN_50") (pintype "output+no_connect"))
    )
    (net (code "131") (name "unconnected-(U2-3vo-Pad2)") (class "Default")
      (node (ref "U2") (pin "2") (pinfunction "3vo_2") (pintype "passive+no_connect"))
    )
    (net (code "132") (name "unconnected-(U2-INT-Pad9)") (class "Default")
      (node (ref "U2") (pin "9") (pinfunction "INT_9") (pintype "passive"))
    )
    (net (code "133") (name "unconnected-(U2-PS0-Pad7)") (class "Default")
      (node (ref "U2") (pin "7") (pinfunction "PS0_7") (pintype "passive"))
    )
    (net (code "134") (name "unconnected-(U2-PS1-Pad8)") (class "Default")
      (node (ref "U2") (pin "8") (pinfunction "PS1_8") (pintype "passive"))
    )
    (net (code "135") (name "unconnected-(X1-NC-Pad2)") (class "Default")
      (node (ref "X1") (pin "2") (pinfunction "NC_2") (pintype "passive+no_connect"))
    )
    (net (code "136") (name "unconnected-(X1-NC-Pad3)") (class "Default")
      (node (ref "X1") (pin "3") (pinfunction "NC_3") (pintype "passive+no_connect"))
    )
  )
)
